# Power.net
KiCad netlist of a schematic drawn in Altium Designer
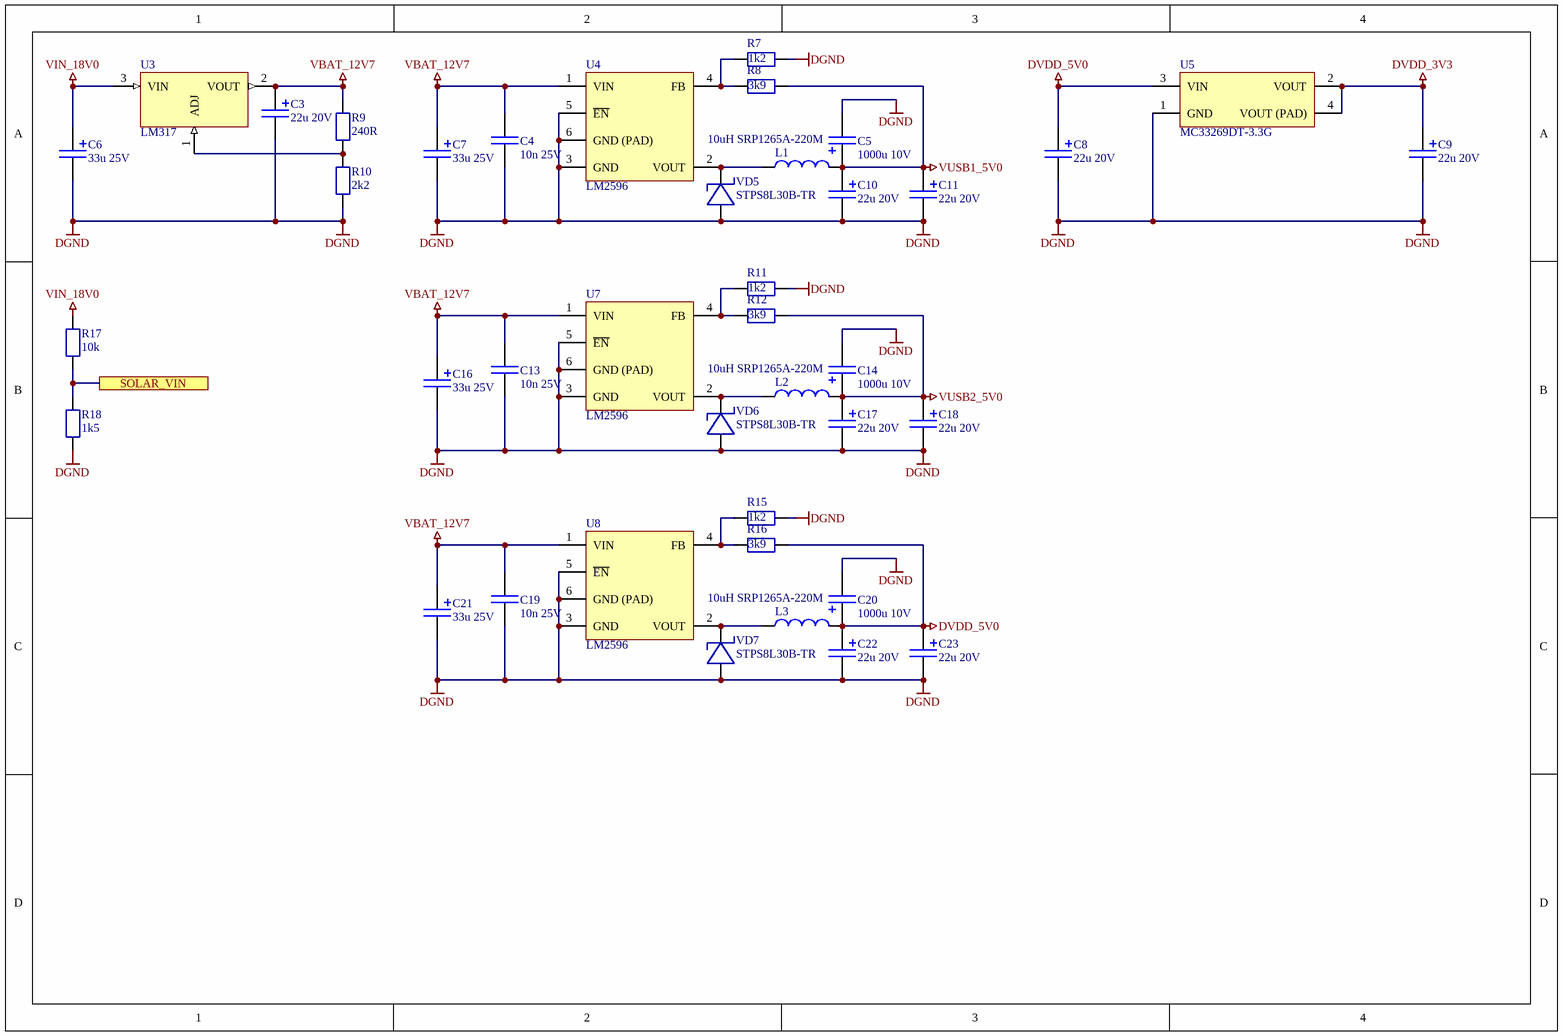
[diagram p0: Power.SchDoc]

(export (version "E")
  (design (tool "Eeschema 10.0.6"))
  (components
    (comp (ref "C3")
      (value "22u 20V")
      (footprint "TECAP_TYPE_B")
      (description "Polarized capacitor\r\n(9000629220)")
      (libsource (lib "passive") (part "Capacitor polar"))
    )
    (comp (ref "C4")
      (value "10n 25V")
      (footprint "C_0805/2012")
      (description "Non-polarized capacitor")
      (libsource (lib "passive") (part "Capacitor"))
    )
    (comp (ref "C5")
      (value "1000u 10V")
      (footprint "ECAP_D10.0x10.5")
      (description "Polarized capacitor")
      (libsource (lib "passive") (part "Capacitor polar"))
    )
    (comp (ref "C6")
      (value "33u 25V")
      (footprint "TECAP_TYPE_B")
      (description "Polarized capacitor\r\n(9000629234)")
      (libsource (lib "passive") (part "Capacitor polar"))
    )
    (comp (ref "C7")
      (value "33u 25V")
      (footprint "TECAP_TYPE_C")
      (description "Polarized capacitor\r\n(9000629234)")
      (libsource (lib "passive") (part "Capacitor polar"))
    )
    (comp (ref "C8")
      (value "22u 20V")
      (footprint "TECAP_TYPE_B")
      (description "Polarized capacitor\r\n(9000629220)")
      (libsource (lib "passive") (part "Capacitor polar"))
    )
    (comp (ref "C9")
      (value "22u 20V")
      (footprint "TECAP_TYPE_B")
      (description "Polarized capacitor\r\n(9000629220)")
      (libsource (lib "passive") (part "Capacitor polar"))
    )
    (comp (ref "C10")
      (value "22u 20V")
      (footprint "TECAP_TYPE_D")
      (description "Polarized capacitor\r\n(9000629220)")
      (libsource (lib "passive") (part "Capacitor polar"))
    )
    (comp (ref "C11")
      (value "22u 20V")
      (footprint "TECAP_TYPE_D")
      (description "Polarized capacitor\r\n(9000629220)")
      (libsource (lib "passive") (part "Capacitor polar"))
    )
    (comp (ref "C13")
      (value "10n 25V")
      (footprint "C_0805/2012")
      (description "Non-polarized capacitor")
      (libsource (lib "passive") (part "Capacitor"))
    )
    (comp (ref "C14")
      (value "1000u 10V")
      (footprint "ECAP_D10.0x10.5")
      (description "Polarized capacitor")
      (libsource (lib "passive") (part "Capacitor polar"))
    )
    (comp (ref "C16")
      (value "33u 25V")
      (footprint "TECAP_TYPE_C")
      (description "Polarized capacitor\r\n(9000629234)")
      (libsource (lib "passive") (part "Capacitor polar"))
    )
    (comp (ref "C17")
      (value "22u 20V")
      (footprint "TECAP_TYPE_D")
      (description "Polarized capacitor\r\n(9000629220)")
      (libsource (lib "passive") (part "Capacitor polar"))
    )
    (comp (ref "C18")
      (value "22u 20V")
      (footprint "TECAP_TYPE_D")
      (description "Polarized capacitor\r\n(9000629220)")
      (libsource (lib "passive") (part "Capacitor polar"))
    )
    (comp (ref "C19")
      (value "10n 25V")
      (footprint "C_0805/2012")
      (description "Non-polarized capacitor")
      (libsource (lib "passive") (part "Capacitor"))
    )
    (comp (ref "C20")
      (value "1000u 10V")
      (footprint "ECAP_D10.0x10.5")
      (description "Polarized capacitor")
      (libsource (lib "passive") (part "Capacitor polar"))
    )
    (comp (ref "C21")
      (value "33u 25V")
      (footprint "TECAP_TYPE_C")
      (description "Polarized capacitor\r\n(9000629234)")
      (libsource (lib "passive") (part "Capacitor polar"))
    )
    (comp (ref "C22")
      (value "22u 20V")
      (footprint "TECAP_TYPE_D")
      (description "Polarized capacitor\r\n(9000629220)")
      (libsource (lib "passive") (part "Capacitor polar"))
    )
    (comp (ref "C23")
      (value "22u 20V")
      (footprint "TECAP_TYPE_D")
      (description "Polarized capacitor\r\n(9000629220)")
      (libsource (lib "passive") (part "Capacitor polar"))
    )
    (comp (ref "L1")
      (value "10uH SRP1265A-220M")
      (footprint "L_13x13")
      (description "Inductor")
      (libsource (lib "passive") (part "Inductor"))
    )
    (comp (ref "L2")
      (value "10uH SRP1265A-220M")
      (footprint "L_13x13")
      (description "Inductor")
      (libsource (lib "passive") (part "Inductor"))
    )
    (comp (ref "L3")
      (value "10uH SRP1265A-220M")
      (footprint "L_13x13")
      (description "Inductor")
      (libsource (lib "passive") (part "Inductor"))
    )
    (comp (ref "R7")
      (value "1k2")
      (footprint "R_0805/2012")
      (description "Resistor")
      (libsource (lib "passive") (part "Resistor"))
    )
    (comp (ref "R8")
      (value "3k9")
      (footprint "R_0805/2012")
      (description "Resistor")
      (libsource (lib "passive") (part "Resistor"))
    )
    (comp (ref "R9")
      (value "240R")
      (footprint "R_0603/1608")
      (description "Resistor")
      (libsource (lib "passive") (part "Resistor"))
    )
    (comp (ref "R10")
      (value "2k2")
      (footprint "R_0603/1608")
      (description "Resistor")
      (libsource (lib "passive") (part "Resistor"))
    )
    (comp (ref "R11")
      (value "1k2")
      (footprint "R_0805/2012")
      (description "Resistor")
      (libsource (lib "passive") (part "Resistor"))
    )
    (comp (ref "R12")
      (value "3k9")
      (footprint "R_0805/2012")
      (description "Resistor")
      (libsource (lib "passive") (part "Resistor"))
    )
    (comp (ref "R15")
      (value "1k2")
      (footprint "R_0805/2012")
      (description "Resistor")
      (libsource (lib "passive") (part "Resistor"))
    )
    (comp (ref "R16")
      (value "3k9")
      (footprint "R_0805/2012")
      (description "Resistor")
      (libsource (lib "passive") (part "Resistor"))
    )
    (comp (ref "R17")
      (value "10k")
      (footprint "R_0603/1608")
      (description "Resistor")
      (libsource (lib "passive") (part "Resistor"))
    )
    (comp (ref "R18")
      (value "1k5")
      (footprint "R_0603/1608")
      (description "Resistor")
      (libsource (lib "passive") (part "Resistor"))
    )
    (comp (ref "U3")
      (value "LM317")
      (footprint "TO-220 HOR")
      (description "Linear regulator LM317")
      (libsource (lib "power") (part "LM317"))
    )
    (comp (ref "U4")
      (value "LM2596")
      (footprint "TO263-5/D2PAK-5")
      (description "DC-DC step-down switching regulator")
      (libsource (lib "power") (part "LM2576"))
    )
    (comp (ref "U5")
      (value "MC33269DT-3.3G")
      (footprint "TO252AA/DPAK")
      (description "LDO voltage regulator")
      (libsource (lib "power") (part "LM1117"))
    )
    (comp (ref "U7")
      (value "LM2596")
      (footprint "TO263-5/D2PAK-5")
      (description "DC-DC step-down switching regulator")
      (libsource (lib "power") (part "LM2576"))
    )
    (comp (ref "U8")
      (value "LM2596")
      (footprint "TO263-5/D2PAK-5")
      (description "DC-DC step-down switching regulator")
      (libsource (lib "power") (part "LM2576"))
    )
    (comp (ref "VD5")
      (value "STPS8L30B-TR")
      (footprint "TO252AA/DPAK")
      (description "Schottky diode")
      (libsource (lib "active") (part "Schottky"))
    )
    (comp (ref "VD6")
      (value "STPS8L30B-TR")
      (footprint "TO252AA/DPAK")
      (description "Schottky diode")
      (libsource (lib "active") (part "Schottky"))
    )
    (comp (ref "VD7")
      (value "STPS8L30B-TR")
      (footprint "TO252AA/DPAK")
      (description "Schottky diode")
      (libsource (lib "active") (part "Schottky"))
    )
  )
  (nets
    (net (code "1") (name "/SOLAR_VIN") (class "Default")
      (node (ref "R17") (pin "1") (pintype "passive"))
      (node (ref "R18") (pin "2") (pintype "passive"))
    )
    (net (code "2") (name "DGND") (class "Default")
      (node (ref "C10") (pin "2") (pinfunction "NEG_2") (pintype "passive"))
      (node (ref "C11") (pin "2") (pinfunction "NEG_2") (pintype "passive"))
      (node (ref "C13") (pin "2") (pintype "passive"))
      (node (ref "C14") (pin "2") (pinfunction "NEG_2") (pintype "passive"))
      (node (ref "C16") (pin "2") (pinfunction "NEG_2") (pintype "passive"))
      (node (ref "C17") (pin "2") (pinfunction "NEG_2") (pintype "passive"))
      (node (ref "C18") (pin "2") (pinfunction "NEG_2") (pintype "passive"))
      (node (ref "C19") (pin "2") (pintype "passive"))
      (node (ref "C20") (pin "2") (pinfunction "NEG_2") (pintype "passive"))
      (node (ref "C21") (pin "2") (pinfunction "NEG_2") (pintype "passive"))
      (node (ref "C22") (pin "2") (pinfunction "NEG_2") (pintype "passive"))
      (node (ref "C23") (pin "2") (pinfunction "NEG_2") (pintype "passive"))
      (node (ref "C3") (pin "2") (pinfunction "NEG_2") (pintype "passive"))
      (node (ref "C4") (pin "2") (pintype "passive"))
      (node (ref "C5") (pin "2") (pinfunction "NEG_2") (pintype "passive"))
      (node (ref "C6") (pin "2") (pinfunction "NEG_2") (pintype "passive"))
      (node (ref "C7") (pin "2") (pinfunction "NEG_2") (pintype "passive"))
      (node (ref "C8") (pin "2") (pinfunction "NEG_2") (pintype "passive"))
      (node (ref "C9") (pin "2") (pinfunction "NEG_2") (pintype "passive"))
      (node (ref "R10") (pin "1") (pintype "passive"))
      (node (ref "R11") (pin "1") (pintype "passive"))
      (node (ref "R15") (pin "1") (pintype "passive"))
      (node (ref "R18") (pin "1") (pintype "passive"))
      (node (ref "R7") (pin "1") (pintype "passive"))
      (node (ref "U4") (pin "3") (pinfunction "GND_3") (pintype "passive"))
      (node (ref "U4") (pin "5") (pinfunction "~{EN}_5") (pintype "passive"))
      (node (ref "U4") (pin "6") (pinfunction "GND_(PAD)_6") (pintype "passive"))
      (node (ref "U5") (pin "1") (pinfunction "GND_1") (pintype "power_in"))
      (node (ref "U7") (pin "3") (pinfunction "GND_3") (pintype "passive"))
      (node (ref "U7") (pin "5") (pinfunction "~{EN}_5") (pintype "passive"))
      (node (ref "U7") (pin "6") (pinfunction "GND_(PAD)_6") (pintype "passive"))
      (node (ref "U8") (pin "3") (pinfunction "GND_3") (pintype "passive"))
      (node (ref "U8") (pin "5") (pinfunction "~{EN}_5") (pintype "passive"))
      (node (ref "U8") (pin "6") (pinfunction "GND_(PAD)_6") (pintype "passive"))
      (node (ref "VD5") (pin "1") (pinfunction "1_1") (pintype "passive"))
      (node (ref "VD6") (pin "1") (pinfunction "1_1") (pintype "passive"))
      (node (ref "VD7") (pin "1") (pinfunction "1_1") (pintype "passive"))
    )
    (net (code "3") (name "DVDD_3V3") (class "Default")
      (node (ref "C9") (pin "1") (pinfunction "POS_1") (pintype "passive"))
      (node (ref "U5") (pin "2") (pinfunction "VOUT_2") (pintype "power_in"))
      (node (ref "U5") (pin "4") (pinfunction "VOUT_(PAD)_4") (pintype "power_in"))
    )
    (net (code "4") (name "DVDD_5V0") (class "Default")
      (node (ref "C20") (pin "1") (pinfunction "POS_1") (pintype "passive"))
      (node (ref "C22") (pin "1") (pinfunction "POS_1") (pintype "passive"))
      (node (ref "C23") (pin "1") (pinfunction "POS_1") (pintype "passive"))
      (node (ref "C8") (pin "1") (pinfunction "POS_1") (pintype "passive"))
      (node (ref "L3") (pin "2") (pintype "passive"))
      (node (ref "R16") (pin "1") (pintype "passive"))
      (node (ref "U5") (pin "3") (pinfunction "VIN_3") (pintype "power_in"))
    )
    (net (code "5") (name "Net-(U3-ADJ)") (class "Default")
      (node (ref "R10") (pin "2") (pintype "passive"))
      (node (ref "R9") (pin "1") (pintype "passive"))
      (node (ref "U3") (pin "1") (pinfunction "ADJ_1") (pintype "input"))
    )
    (net (code "6") (name "Net-(U4-FB)") (class "Default")
      (node (ref "R7") (pin "2") (pintype "passive"))
      (node (ref "R8") (pin "2") (pintype "passive"))
      (node (ref "U4") (pin "4") (pinfunction "FB_4") (pintype "passive"))
    )
    (net (code "7") (name "Net-(U4-VOUT)") (class "Default")
      (node (ref "L1") (pin "1") (pintype "passive"))
      (node (ref "U4") (pin "2") (pinfunction "VOUT_2") (pintype "passive"))
      (node (ref "VD5") (pin "2") (pinfunction "2_2") (pintype "passive"))
    )
    (net (code "8") (name "Net-(U7-FB)") (class "Default")
      (node (ref "R11") (pin "2") (pintype "passive"))
      (node (ref "R12") (pin "2") (pintype "passive"))
      (node (ref "U7") (pin "4") (pinfunction "FB_4") (pintype "passive"))
    )
    (net (code "9") (name "Net-(U7-VOUT)") (class "Default")
      (node (ref "L2") (pin "1") (pintype "passive"))
      (node (ref "U7") (pin "2") (pinfunction "VOUT_2") (pintype "passive"))
      (node (ref "VD6") (pin "2") (pinfunction "2_2") (pintype "passive"))
    )
    (net (code "10") (name "Net-(U8-FB)") (class "Default")
      (node (ref "R15") (pin "2") (pintype "passive"))
      (node (ref "R16") (pin "2") (pintype "passive"))
      (node (ref "U8") (pin "4") (pinfunction "FB_4") (pintype "passive"))
    )
    (net (code "11") (name "Net-(U8-VOUT)") (class "Default")
      (node (ref "L3") (pin "1") (pintype "passive"))
      (node (ref "U8") (pin "2") (pinfunction "VOUT_2") (pintype "passive"))
      (node (ref "VD7") (pin "2") (pinfunction "2_2") (pintype "passive"))
    )
    (net (code "12") (name "VBAT_12V7") (class "Default")
      (node (ref "C13") (pin "1") (pintype "passive"))
      (node (ref "C16") (pin "1") (pinfunction "POS_1") (pintype "passive"))
      (node (ref "C19") (pin "1") (pintype "passive"))
      (node (ref "C21") (pin "1") (pinfunction "POS_1") (pintype "passive"))
      (node (ref "C3") (pin "1") (pinfunction "POS_1") (pintype "passive"))
      (node (ref "C4") (pin "1") (pintype "passive"))
      (node (ref "C7") (pin "1") (pinfunction "POS_1") (pintype "passive"))
      (node (ref "R9") (pin "2") (pintype "passive"))
      (node (ref "U3") (pin "2") (pinfunction "VOUT_2") (pintype "output"))
      (node (ref "U4") (pin "1") (pinfunction "VIN_1") (pintype "passive"))
      (node (ref "U7") (pin "1") (pinfunction "VIN_1") (pintype "passive"))
      (node (ref "U8") (pin "1") (pinfunction "VIN_1") (pintype "passive"))
    )
    (net (code "13") (name "VIN_18V0") (class "Default")
      (node (ref "C6") (pin "1") (pinfunction "POS_1") (pintype "passive"))
      (node (ref "R17") (pin "2") (pintype "passive"))
      (node (ref "U3") (pin "3") (pinfunction "VIN_3") (pintype "input"))
    )
    (net (code "14") (name "VUSB1_5V0") (class "Default")
      (node (ref "C10") (pin "1") (pinfunction "POS_1") (pintype "passive"))
      (node (ref "C11") (pin "1") (pinfunction "POS_1") (pintype "passive"))
      (node (ref "C5") (pin "1") (pinfunction "POS_1") (pintype "passive"))
      (node (ref "L1") (pin "2") (pintype "passive"))
      (node (ref "R8") (pin "1") (pintype "passive"))
    )
    (net (code "15") (name "VUSB2_5V0") (class "Default")
      (node (ref "C14") (pin "1") (pinfunction "POS_1") (pintype "passive"))
      (node (ref "C17") (pin "1") (pinfunction "POS_1") (pintype "passive"))
      (node (ref "C18") (pin "1") (pinfunction "POS_1") (pintype "passive"))
      (node (ref "L2") (pin "2") (pintype "passive"))
      (node (ref "R12") (pin "1") (pintype "passive"))
    )
  )
)
